# synth-zodiac-scorpio-kbd-old.net
KiCad netlist of a schematic drawn in EAGLE
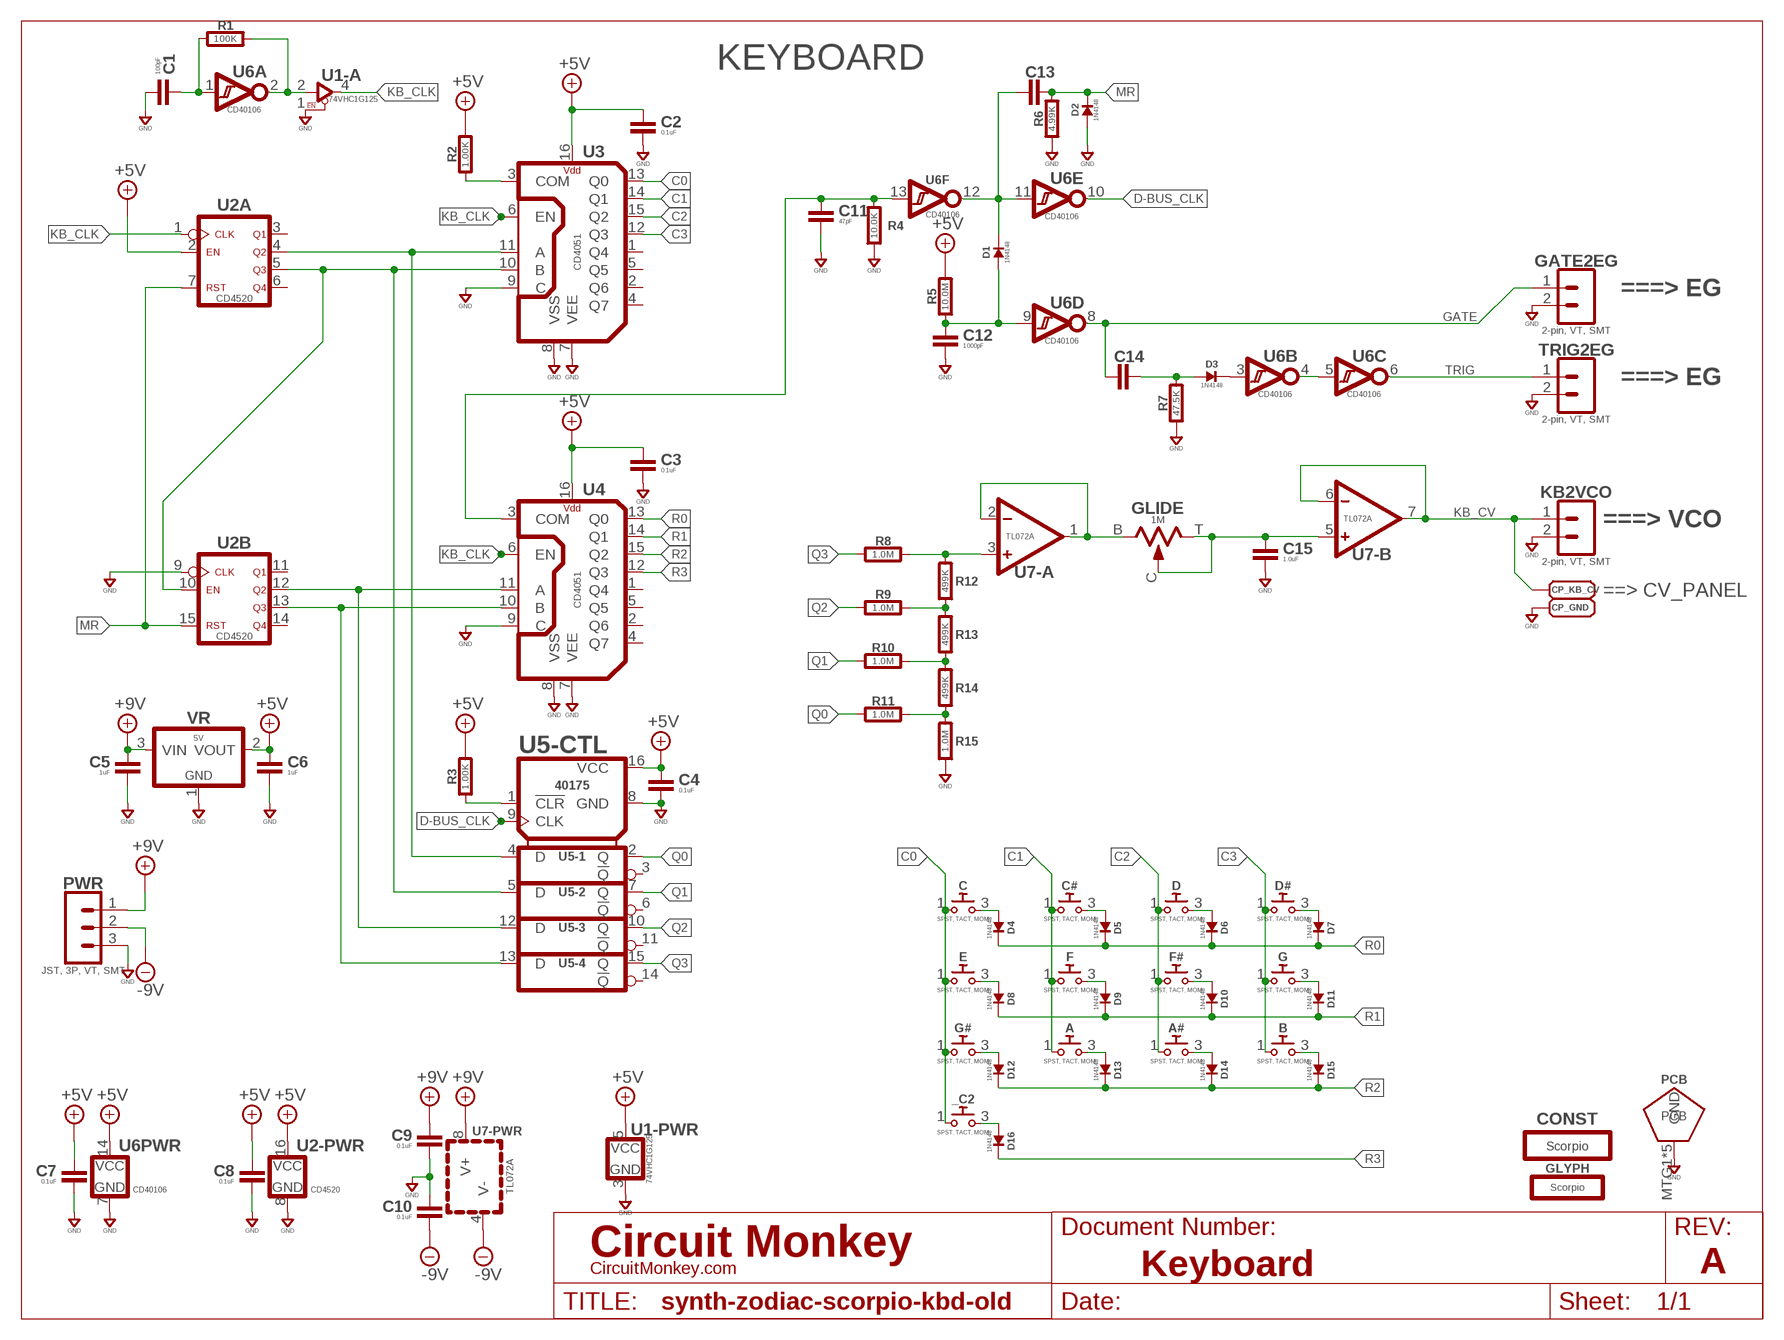
[diagram p0: schematic, sheet 1]

(export (version "E")
  (design (tool "Eeschema 10.0.6"))
  (components
    (comp (ref "A")
      (value "SPST, TACT, MOM")
      (footprint "eagle-import:B3FS-BACKMOUNT")
      (fields (field (name "MFR") "CK") (field (name "MPN") "B3FS"))
      (libsource (lib "eagle-import") (part "PUSHBTN-MOMB3FS-BLIND"))
    )
    (comp (ref "A#")
      (value "SPST, TACT, MOM")
      (footprint "eagle-import:B3FS-BACKMOUNT")
      (fields (field (name "MFR") "CK") (field (name "MPN") "B3FS"))
      (libsource (lib "eagle-import") (part "PUSHBTN-MOMB3FS-BLIND"))
    )
    (comp (ref "B")
      (value "SPST, TACT, MOM")
      (footprint "eagle-import:B3FS-BACKMOUNT")
      (fields (field (name "MFR") "CK") (field (name "MPN") "B3FS"))
      (libsource (lib "eagle-import") (part "PUSHBTN-MOMB3FS-BLIND"))
    )
    (comp (ref "C")
      (value "SPST, TACT, MOM")
      (footprint "eagle-import:B3FS-BACKMOUNT")
      (fields (field (name "MFR") "CK") (field (name "MPN") "B3FS"))
      (libsource (lib "eagle-import") (part "PUSHBTN-MOMB3FS-BLIND"))
    )
    (comp (ref "C#")
      (value "SPST, TACT, MOM")
      (footprint "eagle-import:B3FS-BACKMOUNT")
      (fields (field (name "MFR") "CK") (field (name "MPN") "B3FS"))
      (libsource (lib "eagle-import") (part "PUSHBTN-MOMB3FS-BLIND"))
    )
    (comp (ref "C1")
      (value "100pF")
      (footprint "eagle-import:0603-CAP")
      (libsource (lib "eagle-import") (part "CAPACITOR0603"))
    )
    (comp (ref "C2")
      (value "0.1uF")
      (footprint "eagle-import:0603-CAP")
      (libsource (lib "eagle-import") (part "CAPACITOR0603"))
    )
    (comp (ref "C3")
      (value "0.1uF")
      (footprint "eagle-import:0603-CAP")
      (libsource (lib "eagle-import") (part "CAPACITOR0603"))
    )
    (comp (ref "C4")
      (value "0.1uF")
      (footprint "eagle-import:0603-CAP")
      (libsource (lib "eagle-import") (part "CAPACITOR0603"))
    )
    (comp (ref "C5")
      (value "1uF")
      (footprint "eagle-import:0603-CAP")
      (libsource (lib "eagle-import") (part "CAPACITOR0603"))
    )
    (comp (ref "C6")
      (value "1uF")
      (footprint "eagle-import:0603-CAP")
      (libsource (lib "eagle-import") (part "CAPACITOR0603"))
    )
    (comp (ref "C7")
      (value "0.1uF")
      (footprint "eagle-import:0603-CAP")
      (libsource (lib "eagle-import") (part "CAPACITOR0603"))
    )
    (comp (ref "C8")
      (value "0.1uF")
      (footprint "eagle-import:0603-CAP")
      (libsource (lib "eagle-import") (part "CAPACITOR0603"))
    )
    (comp (ref "C9")
      (value "0.1uF")
      (footprint "eagle-import:0603-CAP")
      (libsource (lib "eagle-import") (part "CAPACITOR0603"))
    )
    (comp (ref "C10")
      (value "0.1uF")
      (footprint "eagle-import:0603-CAP")
      (libsource (lib "eagle-import") (part "CAPACITOR0603"))
    )
    (comp (ref "C11")
      (value "47pF")
      (footprint "eagle-import:0603-CAP")
      (libsource (lib "eagle-import") (part "CAPACITOR0603"))
    )
    (comp (ref "C12")
      (value "1000pF")
      (footprint "eagle-import:0603-CAP")
      (libsource (lib "eagle-import") (part "CAPACITOR0603"))
    )
    (comp (ref "C13")
      (value "220pF")
      (footprint "eagle-import:0603-CAP")
      (libsource (lib "eagle-import") (part "CAPACITOR0603"))
    )
    (comp (ref "C14")
      (value "0.1uF")
      (footprint "eagle-import:0603-CAP")
      (libsource (lib "eagle-import") (part "CAPACITOR0603"))
    )
    (comp (ref "C15")
      (value "1.0uF")
      (footprint "eagle-import:0603-CAP")
      (libsource (lib "eagle-import") (part "CAPACITOR0603"))
    )
    (comp (ref "CONST")
      (value "Scorpio")
      (footprint "eagle-import:SCORPIO-CONST")
      (libsource (lib "eagle-import") (part "CONSTELLATION-SCORPIO"))
    )
    (comp (ref "CP_GND")
      (value "PAD-70X70SMD-070X070")
      (footprint "eagle-import:SMD-070MIL")
      (libsource (lib "eagle-import") (part "PAD-70X70SMD-070X070"))
    )
    (comp (ref "CP_KB_CV")
      (value "PAD-70X70SMD-070X070")
      (footprint "eagle-import:SMD-070MIL")
      (libsource (lib "eagle-import") (part "PAD-70X70SMD-070X070"))
    )
    (comp (ref "D")
      (value "SPST, TACT, MOM")
      (footprint "eagle-import:B3FS-BACKMOUNT")
      (fields (field (name "MFR") "CK") (field (name "MPN") "B3FS"))
      (libsource (lib "eagle-import") (part "PUSHBTN-MOMB3FS-BLIND"))
    )
    (comp (ref "D#")
      (value "SPST, TACT, MOM")
      (footprint "eagle-import:B3FS-BACKMOUNT")
      (fields (field (name "MFR") "CK") (field (name "MPN") "B3FS"))
      (libsource (lib "eagle-import") (part "PUSHBTN-MOMB3FS-BLIND"))
    )
    (comp (ref "D1")
      (value "1N4148")
      (footprint "eagle-import:SOD-123")
      (fields (field (name "MPN") "1N4148W"))
      (libsource (lib "eagle-import") (part "DIODE-1N4148"))
    )
    (comp (ref "D2")
      (value "1N4148")
      (footprint "eagle-import:SOD-123")
      (fields (field (name "MPN") "1N4148W"))
      (libsource (lib "eagle-import") (part "DIODE-1N4148"))
    )
    (comp (ref "D3")
      (value "1N4148")
      (footprint "eagle-import:SOD-123")
      (fields (field (name "MPN") "1N4148W"))
      (libsource (lib "eagle-import") (part "DIODE-1N4148"))
    )
    (comp (ref "D4")
      (value "1N4148")
      (footprint "eagle-import:SOD-123")
      (fields (field (name "MPN") "1N4148W"))
      (libsource (lib "eagle-import") (part "DIODE-1N4148"))
    )
    (comp (ref "D5")
      (value "1N4148")
      (footprint "eagle-import:SOD-123")
      (fields (field (name "MPN") "1N4148W"))
      (libsource (lib "eagle-import") (part "DIODE-1N4148"))
    )
    (comp (ref "D6")
      (value "1N4148")
      (footprint "eagle-import:SOD-123")
      (fields (field (name "MPN") "1N4148W"))
      (libsource (lib "eagle-import") (part "DIODE-1N4148"))
    )
    (comp (ref "D7")
      (value "1N4148")
      (footprint "eagle-import:SOD-123")
      (fields (field (name "MPN") "1N4148W"))
      (libsource (lib "eagle-import") (part "DIODE-1N4148"))
    )
    (comp (ref "D8")
      (value "1N4148")
      (footprint "eagle-import:SOD-123")
      (fields (field (name "MPN") "1N4148W"))
      (libsource (lib "eagle-import") (part "DIODE-1N4148"))
    )
    (comp (ref "D9")
      (value "1N4148")
      (footprint "eagle-import:SOD-123")
      (fields (field (name "MPN") "1N4148W"))
      (libsource (lib "eagle-import") (part "DIODE-1N4148"))
    )
    (comp (ref "D10")
      (value "1N4148")
      (footprint "eagle-import:SOD-123")
      (fields (field (name "MPN") "1N4148W"))
      (libsource (lib "eagle-import") (part "DIODE-1N4148"))
    )
    (comp (ref "D11")
      (value "1N4148")
      (footprint "eagle-import:SOD-123")
      (fields (field (name "MPN") "1N4148W"))
      (libsource (lib "eagle-import") (part "DIODE-1N4148"))
    )
    (comp (ref "D12")
      (value "1N4148")
      (footprint "eagle-import:SOD-123")
      (fields (field (name "MPN") "1N4148W"))
      (libsource (lib "eagle-import") (part "DIODE-1N4148"))
    )
    (comp (ref "D13")
      (value "1N4148")
      (footprint "eagle-import:SOD-123")
      (fields (field (name "MPN") "1N4148W"))
      (libsource (lib "eagle-import") (part "DIODE-1N4148"))
    )
    (comp (ref "D14")
      (value "1N4148")
      (footprint "eagle-import:SOD-123")
      (fields (field (name "MPN") "1N4148W"))
      (libsource (lib "eagle-import") (part "DIODE-1N4148"))
    )
    (comp (ref "D15")
      (value "1N4148")
      (footprint "eagle-import:SOD-123")
      (fields (field (name "MPN") "1N4148W"))
      (libsource (lib "eagle-import") (part "DIODE-1N4148"))
    )
    (comp (ref "D16")
      (value "1N4148")
      (footprint "eagle-import:SOD-123")
      (fields (field (name "MPN") "1N4148W"))
      (libsource (lib "eagle-import") (part "DIODE-1N4148"))
    )
    (comp (ref "E")
      (value "SPST, TACT, MOM")
      (footprint "eagle-import:B3FS-BACKMOUNT")
      (fields (field (name "MFR") "CK") (field (name "MPN") "B3FS"))
      (libsource (lib "eagle-import") (part "PUSHBTN-MOMB3FS-BLIND"))
    )
    (comp (ref "F")
      (value "SPST, TACT, MOM")
      (footprint "eagle-import:B3FS-BACKMOUNT")
      (fields (field (name "MFR") "CK") (field (name "MPN") "B3FS"))
      (libsource (lib "eagle-import") (part "PUSHBTN-MOMB3FS-BLIND"))
    )
    (comp (ref "F#")
      (value "SPST, TACT, MOM")
      (footprint "eagle-import:B3FS-BACKMOUNT")
      (fields (field (name "MFR") "CK") (field (name "MPN") "B3FS"))
      (libsource (lib "eagle-import") (part "PUSHBTN-MOMB3FS-BLIND"))
    )
    (comp (ref "G")
      (value "SPST, TACT, MOM")
      (footprint "eagle-import:B3FS-BACKMOUNT")
      (fields (field (name "MFR") "CK") (field (name "MPN") "B3FS"))
      (libsource (lib "eagle-import") (part "PUSHBTN-MOMB3FS-BLIND"))
    )
    (comp (ref "G#")
      (value "SPST, TACT, MOM")
      (footprint "eagle-import:B3FS-BACKMOUNT")
      (fields (field (name "MFR") "CK") (field (name "MPN") "B3FS"))
      (libsource (lib "eagle-import") (part "PUSHBTN-MOMB3FS-BLIND"))
    )
    (comp (ref "GATE2EG")
      (value "2-pin, VT, SMT")
      (footprint "eagle-import:B2B-PH-SM4")
      (fields (field (name "MFR") "JST") (field (name "MPN") "B2B-PH-SM4"))
      (libsource (lib "eagle-import") (part "02PVT-SMT"))
    )
    (comp (ref "GLIDE")
      (value "1M")
      (footprint "eagle-import:POT-RV9110")
      (fields (field (name "MFR") "Tayda") (field (name "MPN") "RV9110NO-OS15A00"))
      (libsource (lib "eagle-import") (part "TRIMPOT9MM_PCB_SHAFT"))
    )
    (comp (ref "GLYPH")
      (value "Scorpio")
      (footprint "eagle-import:SCORPIO-GLYPH")
      (libsource (lib "eagle-import") (part "GLYPH-SCORPIO"))
    )
    (comp (ref "KB2VCO")
      (value "2-pin, VT, SMT")
      (footprint "eagle-import:B2B-PH-SM4")
      (fields (field (name "MFR") "JST") (field (name "MPN") "B2B-PH-SM4"))
      (libsource (lib "eagle-import") (part "02PVT-SMT"))
    )
    (comp (ref "PCB")
      (value "PCB FAB")
      (footprint "eagle-import:PENTAGON-40MM-RAD")
      (libsource (lib "eagle-import") (part "PENTAGON-40R"))
    )
    (comp (ref "PWR")
      (value "JST, 3P, VT, SMT")
      (footprint "eagle-import:B3B-PH-SM4")
      (fields (field (name "MFR") "JST") (field (name "MPN") "B3B-PH-SM4"))
      (libsource (lib "eagle-import") (part "03P-VT-SMT"))
    )
    (comp (ref "R1")
      (value "100K")
      (footprint "eagle-import:0603-RES")
      (libsource (lib "eagle-import") (part "RESISTOR0603"))
    )
    (comp (ref "R2")
      (value "1.00K")
      (footprint "eagle-import:0603-RES")
      (libsource (lib "eagle-import") (part "RESISTOR0603"))
    )
    (comp (ref "R3")
      (value "1.00K")
      (footprint "eagle-import:0603-RES")
      (libsource (lib "eagle-import") (part "RESISTOR0603"))
    )
    (comp (ref "R4")
      (value "10.0K")
      (footprint "eagle-import:0603-RES")
      (libsource (lib "eagle-import") (part "RESISTOR0603"))
    )
    (comp (ref "R5")
      (value "10.0M")
      (footprint "eagle-import:0603-RES")
      (libsource (lib "eagle-import") (part "RESISTOR0603"))
    )
    (comp (ref "R6")
      (value "4.99K")
      (footprint "eagle-import:0603-RES")
      (libsource (lib "eagle-import") (part "RESISTOR0603"))
    )
    (comp (ref "R7")
      (value "47.5K")
      (footprint "eagle-import:0603-RES")
      (libsource (lib "eagle-import") (part "RESISTOR0603"))
    )
    (comp (ref "R8")
      (value "1.0M")
      (footprint "eagle-import:0603-RES")
      (libsource (lib "eagle-import") (part "RESISTOR0603"))
    )
    (comp (ref "R9")
      (value "1.0M")
      (footprint "eagle-import:0603-RES")
      (libsource (lib "eagle-import") (part "RESISTOR0603"))
    )
    (comp (ref "R10")
      (value "1.0M")
      (footprint "eagle-import:0603-RES")
      (libsource (lib "eagle-import") (part "RESISTOR0603"))
    )
    (comp (ref "R11")
      (value "1.0M")
      (footprint "eagle-import:0603-RES")
      (libsource (lib "eagle-import") (part "RESISTOR0603"))
    )
    (comp (ref "R12")
      (value "499K")
      (footprint "eagle-import:0603-RES")
      (libsource (lib "eagle-import") (part "RESISTOR0603"))
    )
    (comp (ref "R13")
      (value "499K")
      (footprint "eagle-import:0603-RES")
      (libsource (lib "eagle-import") (part "RESISTOR0603"))
    )
    (comp (ref "R14")
      (value "499K")
      (footprint "eagle-import:0603-RES")
      (libsource (lib "eagle-import") (part "RESISTOR0603"))
    )
    (comp (ref "R15")
      (value "1.0M")
      (footprint "eagle-import:0603-RES")
      (libsource (lib "eagle-import") (part "RESISTOR0603"))
    )
    (comp (ref "TRIG2EG")
      (value "2-pin, VT, SMT")
      (footprint "eagle-import:B2B-PH-SM4")
      (fields (field (name "MFR") "JST") (field (name "MPN") "B2B-PH-SM4"))
      (libsource (lib "eagle-import") (part "02PVT-SMT"))
    )
    (comp (ref "U1")
      (value "74VHC1G125")
      (footprint "eagle-import:TSOP-5")
      (fields (field (name "MFR") "ON Semi") (field (name "MPN") "MC74VHC1G125P5TG"))
      (libsource (lib "eagle-import") (part "74VHC1G125CMOS-SOT553"))
    )
    (comp (ref "U2")
      (value "CD4520")
      (footprint "eagle-import:SO16")
      (fields (field (name "MFR") "TI") (field (name "MPN") "CD4520BM96"))
      (libsource (lib "eagle-import") (part "CD4520"))
    )
    (comp (ref "U3")
      (value "CD4051")
      (footprint "eagle-import:SO16")
      (fields (field (name "MFR") "TI") (field (name "MPN") "CD4051BM"))
      (libsource (lib "eagle-import") (part "CD4051SO-D"))
    )
    (comp (ref "U4")
      (value "CD4051")
      (footprint "eagle-import:SO16")
      (fields (field (name "MFR") "TI") (field (name "MPN") "CD4051BM"))
      (libsource (lib "eagle-import") (part "CD4051SO-D"))
    )
    (comp (ref "U5")
      (value "40175")
      (footprint "eagle-import:SO16")
      (fields (field (name "MFR") "TI") (field (name "MPN") "CD40175BM"))
      (libsource (lib "eagle-import") (part "CD40175SMT-D-TYPE"))
    )
    (comp (ref "U6")
      (value "CD40106")
      (footprint "eagle-import:SOP14")
      (fields (field (name "MFR") "TI") (field (name "MPN") "CD40106BM"))
      (libsource (lib "eagle-import") (part "CD40106-SOP14"))
    )
    (comp (ref "U7")
      (value "TL072A")
      (footprint "eagle-import:SOP08")
      (fields (field (name "MFR") "ST"))
      (libsource (lib "eagle-import") (part "DUALTL072A"))
    )
    (comp (ref "VR")
      (value "5V")
      (footprint "eagle-import:SOT-23")
      (fields (field (name "MFR") "Diodes, Inc.") (field (name "MPN") "AP7387-50SA"))
      (libsource (lib "eagle-import") (part "LDO-3P--5V-SOT23"))
    )
    (comp (ref "_C2")
      (value "SPST, TACT, MOM")
      (footprint "eagle-import:B3FS-BACKMOUNT")
      (fields (field (name "MFR") "CK") (field (name "MPN") "B3FS"))
      (libsource (lib "eagle-import") (part "PUSHBTN-MOMB3FS-BLIND"))
    )
  )
  (nets
    (net (code "1") (name "+5V") (class "Default")
      (node (ref "C2") (pin "1") (pinfunction "1_1") (pintype "passive"))
      (node (ref "C3") (pin "1") (pinfunction "1_1") (pintype "passive"))
      (node (ref "C4") (pin "1") (pinfunction "1_1") (pintype "passive"))
      (node (ref "C6") (pin "1") (pinfunction "1_1") (pintype "passive"))
      (node (ref "C7") (pin "1") (pinfunction "1_1") (pintype "passive"))
      (node (ref "C8") (pin "1") (pinfunction "1_1") (pintype "passive"))
      (node (ref "R2") (pin "2") (pinfunction "2_2") (pintype "passive"))
      (node (ref "R3") (pin "2") (pinfunction "2_2") (pintype "passive"))
      (node (ref "R5") (pin "2") (pinfunction "2_2") (pintype "passive"))
      (node (ref "U1") (pin "5") (pinfunction "VCC_5") (pintype "power_in"))
      (node (ref "U2") (pin "16") (pinfunction "VCC_16") (pintype "power_in"))
      (node (ref "U2") (pin "2") (pinfunction "EN_2") (pintype "input"))
      (node (ref "U3") (pin "16") (pinfunction "VDD_16") (pintype "power_in"))
      (node (ref "U4") (pin "16") (pinfunction "VDD_16") (pintype "power_in"))
      (node (ref "U5") (pin "16") (pinfunction "VCC_16") (pintype "power_in"))
      (node (ref "U6") (pin "14") (pinfunction "VCC_14") (pintype "power_in"))
      (node (ref "VR") (pin "2") (pinfunction "VOUT_2") (pintype "power_in"))
    )
    (net (code "2") (name "+9V") (class "Default")
      (node (ref "C5") (pin "1") (pinfunction "1_1") (pintype "passive"))
      (node (ref "C9") (pin "1") (pinfunction "1_1") (pintype "passive"))
      (node (ref "PWR") (pin "1") (pinfunction "1_1") (pintype "passive"))
      (node (ref "U7") (pin "8") (pinfunction "V+_8") (pintype "power_in"))
      (node (ref "VR") (pin "3") (pinfunction "VIN_3") (pintype "power_in"))
    )
    (net (code "3") (name "-9V") (class "Default")
      (node (ref "C10") (pin "2") (pinfunction "2_2") (pintype "passive"))
      (node (ref "PWR") (pin "2") (pinfunction "2_2") (pintype "passive"))
      (node (ref "U7") (pin "4") (pinfunction "V-_4") (pintype "power_in"))
    )
    (net (code "4") (name "/GATE") (class "Default")
      (node (ref "C14") (pin "1") (pinfunction "1_1") (pintype "passive"))
      (node (ref "GATE2EG") (pin "1") (pinfunction "1_1") (pintype "passive"))
      (node (ref "U6") (pin "8") (pinfunction "Y_8") (pintype "bidirectional"))
    )
    (net (code "5") (name "/KB_CV") (class "Default")
      (node (ref "CP_KB_CV") (pin "1") (pinfunction "PAD_1") (pintype "bidirectional"))
      (node (ref "KB2VCO") (pin "1") (pinfunction "1_1") (pintype "passive"))
      (node (ref "U7") (pin "6") (pinfunction "-_6") (pintype "input"))
      (node (ref "U7") (pin "7") (pinfunction "OUT_7") (pintype "output"))
    )
    (net (code "6") (name "/TRIG") (class "Default")
      (node (ref "TRIG2EG") (pin "1") (pinfunction "1_1") (pintype "passive"))
      (node (ref "U6") (pin "6") (pinfunction "Y_6") (pintype "bidirectional"))
    )
    (net (code "7") (name "C0") (class "Default")
      (node (ref "C") (pin "1") (pinfunction "1_1") (pintype "passive"))
      (node (ref "E") (pin "1") (pinfunction "1_1") (pintype "passive"))
      (node (ref "G#") (pin "1") (pinfunction "1_1") (pintype "passive"))
      (node (ref "U3") (pin "13") (pinfunction "Q0_13") (pintype "bidirectional"))
      (node (ref "_C2") (pin "1") (pinfunction "1_1") (pintype "passive"))
    )
    (net (code "8") (name "C1") (class "Default")
      (node (ref "A") (pin "1") (pinfunction "1_1") (pintype "passive"))
      (node (ref "C#") (pin "1") (pinfunction "1_1") (pintype "passive"))
      (node (ref "F") (pin "1") (pinfunction "1_1") (pintype "passive"))
      (node (ref "U3") (pin "14") (pinfunction "Q1_14") (pintype "bidirectional"))
    )
    (net (code "9") (name "C2") (class "Default")
      (node (ref "A#") (pin "1") (pinfunction "1_1") (pintype "passive"))
      (node (ref "D") (pin "1") (pinfunction "1_1") (pintype "passive"))
      (node (ref "F#") (pin "1") (pinfunction "1_1") (pintype "passive"))
      (node (ref "U3") (pin "15") (pinfunction "Q2_15") (pintype "bidirectional"))
    )
    (net (code "10") (name "C3") (class "Default")
      (node (ref "B") (pin "1") (pinfunction "1_1") (pintype "passive"))
      (node (ref "D#") (pin "1") (pinfunction "1_1") (pintype "passive"))
      (node (ref "G") (pin "1") (pinfunction "1_1") (pintype "passive"))
      (node (ref "U3") (pin "12") (pinfunction "Q3_12") (pintype "bidirectional"))
    )
    (net (code "11") (name "D-BUS_CLK") (class "Default")
      (node (ref "U5") (pin "9") (pinfunction "CLK_9") (pintype "input"))
      (node (ref "U6") (pin "10") (pinfunction "Y_10") (pintype "bidirectional"))
    )
    (net (code "12") (name "GND") (class "Default")
      (node (ref "C1") (pin "2") (pinfunction "2_2") (pintype "passive"))
      (node (ref "C10") (pin "1") (pinfunction "1_1") (pintype "passive"))
      (node (ref "C11") (pin "2") (pinfunction "2_2") (pintype "passive"))
      (node (ref "C12") (pin "2") (pinfunction "2_2") (pintype "passive"))
      (node (ref "C15") (pin "2") (pinfunction "2_2") (pintype "passive"))
      (node (ref "C2") (pin "2") (pinfunction "2_2") (pintype "passive"))
      (node (ref "C3") (pin "2") (pinfunction "2_2") (pintype "passive"))
      (node (ref "C4") (pin "2") (pinfunction "2_2") (pintype "passive"))
      (node (ref "C5") (pin "2") (pinfunction "2_2") (pintype "passive"))
      (node (ref "C6") (pin "2") (pinfunction "2_2") (pintype "passive"))
      (node (ref "C7") (pin "2") (pinfunction "2_2") (pintype "passive"))
      (node (ref "C8") (pin "2") (pinfunction "2_2") (pintype "passive"))
      (node (ref "C9") (pin "2") (pinfunction "2_2") (pintype "passive"))
      (node (ref "CP_GND") (pin "1") (pinfunction "PAD_1") (pintype "bidirectional"))
      (node (ref "D2") (pin "A") (pinfunction "A_A") (pintype "passive"))
      (node (ref "GATE2EG") (pin "2") (pinfunction "2_2") (pintype "passive"))
      (node (ref "KB2VCO") (pin "2") (pinfunction "2_2") (pintype "passive"))
      (node (ref "PCB") (pin "MTG1") (pinfunction "GND_MTG1") (pintype "bidirectional"))
      (node (ref "PCB") (pin "MTG2") (pinfunction "GND_MTG2") (pintype "bidirectional"))
      (node (ref "PCB") (pin "MTG3") (pinfunction "GND_MTG3") (pintype "bidirectional"))
      (node (ref "PCB") (pin "MTG4") (pinfunction "GND_MTG4") (pintype "bidirectional"))
      (node (ref "PCB") (pin "MTG5") (pinfunction "GND_MTG5") (pintype "bidirectional"))
      (node (ref "PWR") (pin "3") (pinfunction "3_3") (pintype "passive"))
      (node (ref "R15") (pin "1") (pinfunction "1_1") (pintype "passive"))
      (node (ref "R4") (pin "1") (pinfunction "1_1") (pintype "passive"))
      (node (ref "R6") (pin "1") (pinfunction "1_1") (pintype "passive"))
      (node (ref "R7") (pin "1") (pinfunction "1_1") (pintype "passive"))
      (node (ref "TRIG2EG") (pin "2") (pinfunction "2_2") (pintype "passive"))
      (node (ref "U1") (pin "1") (pinfunction "~{EN}_1") (pintype "input"))
      (node (ref "U1") (pin "3") (pinfunction "GND_3") (pintype "power_in"))
      (node (ref "U2") (pin "8") (pinfunction "GND_8") (pintype "power_in"))
      (node (ref "U2") (pin "9") (pinfunction "~{CLK}_9") (pintype "input"))
      (node (ref "U3") (pin "7") (pinfunction "VEE_7") (pintype "power_in"))
      (node (ref "U3") (pin "8") (pinfunction "VSS_8") (pintype "power_in"))
      (node (ref "U3") (pin "9") (pinfunction "C_9") (pintype "input"))
      (node (ref "U4") (pin "7") (pinfunction "VEE_7") (pintype "power_in"))
      (node (ref "U4") (pin "8") (pinfunction "VSS_8") (pintype "power_in"))
      (node (ref "U4") (pin "9") (pinfunction "C_9") (pintype "input"))
      (node (ref "U5") (pin "8") (pinfunction "GND_8") (pintype "power_in"))
      (node (ref "U6") (pin "7") (pinfunction "GND_7") (pintype "power_in"))
      (node (ref "VR") (pin "1") (pinfunction "GND_1") (pintype "power_in"))
    )
    (net (code "13") (name "KB_CLK") (class "Default")
      (node (ref "U1") (pin "4") (pinfunction "Y_4") (pintype "output"))
      (node (ref "U2") (pin "1") (pinfunction "~{CLK}_1") (pintype "input"))
      (node (ref "U3") (pin "6") (pinfunction "EN_6") (pintype "input"))
      (node (ref "U4") (pin "6") (pinfunction "EN_6") (pintype "input"))
    )
    (net (code "14") (name "MR") (class "Default")
      (node (ref "C13") (pin "2") (pinfunction "2_2") (pintype "passive"))
      (node (ref "D2") (pin "K") (pinfunction "K_K") (pintype "passive"))
      (node (ref "R6") (pin "2") (pinfunction "2_2") (pintype "passive"))
      (node (ref "U2") (pin "15") (pinfunction "RST_15") (pintype "input"))
      (node (ref "U2") (pin "7") (pinfunction "RST_7") (pintype "input"))
    )
    (net (code "15") (name "Net-(A#-2)") (class "Default")
      (node (ref "A#") (pin "3") (pinfunction "2_3") (pintype "passive"))
      (node (ref "D14") (pin "A") (pinfunction "A_A") (pintype "passive"))
    )
    (net (code "16") (name "Net-(A-2)") (class "Default")
      (node (ref "A") (pin "3") (pinfunction "2_3") (pintype "passive"))
      (node (ref "D13") (pin "A") (pinfunction "A_A") (pintype "passive"))
    )
    (net (code "17") (name "Net-(B-2)") (class "Default")
      (node (ref "B") (pin "3") (pinfunction "2_3") (pintype "passive"))
      (node (ref "D15") (pin "A") (pinfunction "A_A") (pintype "passive"))
    )
    (net (code "18") (name "Net-(C#-2)") (class "Default")
      (node (ref "C#") (pin "3") (pinfunction "2_3") (pintype "passive"))
      (node (ref "D5") (pin "A") (pinfunction "A_A") (pintype "passive"))
    )
    (net (code "19") (name "Net-(C-2)") (class "Default")
      (node (ref "C") (pin "3") (pinfunction "2_3") (pintype "passive"))
      (node (ref "D4") (pin "A") (pinfunction "A_A") (pintype "passive"))
    )
    (net (code "20") (name "Net-(C14-Pad2)") (class "Default")
      (node (ref "C14") (pin "2") (pinfunction "2_2") (pintype "passive"))
      (node (ref "D3") (pin "A") (pinfunction "A_A") (pintype "passive"))
      (node (ref "R7") (pin "2") (pinfunction "2_2") (pintype "passive"))
    )
    (net (code "21") (name "Net-(D#-2)") (class "Default")
      (node (ref "D#") (pin "3") (pinfunction "2_3") (pintype "passive"))
      (node (ref "D7") (pin "A") (pinfunction "A_A") (pintype "passive"))
    )
    (net (code "22") (name "Net-(D-2)") (class "Default")
      (node (ref "D") (pin "3") (pinfunction "2_3") (pintype "passive"))
      (node (ref "D6") (pin "A") (pinfunction "A_A") (pintype "passive"))
    )
    (net (code "23") (name "Net-(E-2)") (class "Default")
      (node (ref "D8") (pin "A") (pinfunction "A_A") (pintype "passive"))
      (node (ref "E") (pin "3") (pinfunction "2_3") (pintype "passive"))
    )
    (net (code "24") (name "Net-(F#-2)") (class "Default")
      (node (ref "D10") (pin "A") (pinfunction "A_A") (pintype "passive"))
      (node (ref "F#") (pin "3") (pinfunction "2_3") (pintype "passive"))
    )
    (net (code "25") (name "Net-(F-2)") (class "Default")
      (node (ref "D9") (pin "A") (pinfunction "A_A") (pintype "passive"))
      (node (ref "F") (pin "3") (pinfunction "2_3") (pintype "passive"))
    )
    (net (code "26") (name "Net-(G#-2)") (class "Default")
      (node (ref "D12") (pin "A") (pinfunction "A_A") (pintype "passive"))
      (node (ref "G#") (pin "3") (pinfunction "2_3") (pintype "passive"))
    )
    (net (code "27") (name "Net-(G-2)") (class "Default")
      (node (ref "D11") (pin "A") (pinfunction "A_A") (pintype "passive"))
      (node (ref "G") (pin "3") (pinfunction "2_3") (pintype "passive"))
    )
    (net (code "28") (name "Net-(GLIDE-1)") (class "Default")
      (node (ref "GLIDE") (pin "B") (pinfunction "1_B") (pintype "passive"))
      (node (ref "U7") (pin "1") (pinfunction "OUT_1") (pintype "output"))
      (node (ref "U7") (pin "2") (pinfunction "-_2") (pintype "input"))
    )
    (net (code "29") (name "Net-(GLIDE-2)") (class "Default")
      (node (ref "C15") (pin "1") (pinfunction "1_1") (pintype "passive"))
      (node (ref "GLIDE") (pin "C") (pinfunction "2_C") (pintype "passive"))
      (node (ref "GLIDE") (pin "T") (pinfunction "3_T") (pintype "passive"))
      (node (ref "U7") (pin "5") (pinfunction "+_5") (pintype "input"))
    )
    (net (code "30") (name "Net-(R10-Pad2)") (class "Default")
      (node (ref "R10") (pin "2") (pinfunction "2_2") (pintype "passive"))
      (node (ref "R13") (pin "1") (pinfunction "1_1") (pintype "passive"))
      (node (ref "R14") (pin "2") (pinfunction "2_2") (pintype "passive"))
    )
    (net (code "31") (name "Net-(R11-Pad2)") (class "Default")
      (node (ref "R11") (pin "2") (pinfunction "2_2") (pintype "passive"))
      (node (ref "R14") (pin "1") (pinfunction "1_1") (pintype "passive"))
      (node (ref "R15") (pin "2") (pinfunction "2_2") (pintype "passive"))
    )
    (net (code "32") (name "Net-(R12-Pad1)") (class "Default")
      (node (ref "R12") (pin "1") (pinfunction "1_1") (pintype "passive"))
      (node (ref "R13") (pin "2") (pinfunction "2_2") (pintype "passive"))
      (node (ref "R9") (pin "2") (pinfunction "2_2") (pintype "passive"))
    )
    (net (code "33") (name "Net-(U1A-A)") (class "Default")
      (node (ref "R1") (pin "2") (pinfunction "2_2") (pintype "passive"))
      (node (ref "U1") (pin "2") (pinfunction "A_2") (pintype "input"))
      (node (ref "U6") (pin "2") (pinfunction "Y_2") (pintype "bidirectional"))
    )
    (net (code "34") (name "Net-(U2B-Q2)") (class "Default")
      (node (ref "U2") (pin "4") (pinfunction "Q2_4") (pintype "output"))
      (node (ref "U3") (pin "11") (pinfunction "A_11") (pintype "input"))
      (node (ref "U5") (pin "4") (pinfunction "D_4") (pintype "input"))
    )
    (net (code "35") (name "Net-(U2B-Q3)") (class "Default")
      (node (ref "U2") (pin "10") (pinfunction "EN_10") (pintype "input"))
      (node (ref "U2") (pin "5") (pinfunction "Q3_5") (pintype "output"))
      (node (ref "U3") (pin "10") (pinfunction "B_10") (pintype "input"))
      (node (ref "U5") (pin "5") (pinfunction "D_5") (pintype "input"))
    )
    (net (code "36") (name "Net-(U2C-Q2)") (class "Default")
      (node (ref "U2") (pin "12") (pinfunction "Q2_12") (pintype "output"))
      (node (ref "U4") (pin "11") (pinfunction "A_11") (pintype "input"))
      (node (ref "U5") (pin "12") (pinfunction "D_12") (pintype "input"))
    )
    (net (code "37") (name "Net-(U2C-Q3)") (class "Default")
      (node (ref "U2") (pin "13") (pinfunction "Q3_13") (pintype "output"))
      (node (ref "U4") (pin "10") (pinfunction "B_10") (pintype "input"))
      (node (ref "U5") (pin "13") (pinfunction "D_13") (pintype "input"))
    )
    (net (code "38") (name "Net-(U3-COM)") (class "Default")
      (node (ref "R2") (pin "1") (pinfunction "1_1") (pintype "passive"))
      (node (ref "U3") (pin "3") (pinfunction "COM_3") (pintype "bidirectional"))
    )
    (net (code "39") (name "Net-(U4-COM)") (class "Default")
      (node (ref "C11") (pin "1") (pinfunction "1_1") (pintype "passive"))
      (node (ref "R4") (pin "2") (pinfunction "2_2") (pintype "passive"))
      (node (ref "U4") (pin "3") (pinfunction "COM_3") (pintype "bidirectional"))
      (node (ref "U6") (pin "13") (pinfunction "A_13") (pintype "bidirectional"))
    )
    (net (code "40") (name "Net-(U5E-~{CLR})") (class "Default")
      (node (ref "R3") (pin "1") (pinfunction "1_1") (pintype "passive"))
      (node (ref "U5") (pin "1") (pinfunction "~{CLR}_1") (pintype "input"))
    )
    (net (code "41") (name "Net-(U6A-A)") (class "Default")
      (node (ref "C1") (pin "1") (pinfunction "1_1") (pintype "passive"))
      (node (ref "R1") (pin "1") (pinfunction "1_1") (pintype "passive"))
      (node (ref "U6") (pin "1") (pinfunction "A_1") (pintype "bidirectional"))
    )
    (net (code "42") (name "Net-(U6B-A)") (class "Default")
      (node (ref "D3") (pin "K") (pinfunction "K_K") (pintype "passive"))
      (node (ref "U6") (pin "3") (pinfunction "A_3") (pintype "bidirectional"))
    )
    (net (code "43") (name "Net-(U6B-Y)") (class "Default")
      (node (ref "U6") (pin "4") (pinfunction "Y_4") (pintype "bidirectional"))
      (node (ref "U6") (pin "5") (pinfunction "A_5") (pintype "bidirectional"))
    )
    (net (code "44") (name "Net-(U6D-A)") (class "Default")
      (node (ref "C12") (pin "1") (pinfunction "1_1") (pintype "passive"))
      (node (ref "D1") (pin "A") (pinfunction "A_A") (pintype "passive"))
      (node (ref "R5") (pin "1") (pinfunction "1_1") (pintype "passive"))
      (node (ref "U6") (pin "9") (pinfunction "A_9") (pintype "bidirectional"))
    )
    (net (code "45") (name "Net-(U6E-A)") (class "Default")
      (node (ref "C13") (pin "1") (pinfunction "1_1") (pintype "passive"))
      (node (ref "D1") (pin "K") (pinfunction "K_K") (pintype "passive"))
      (node (ref "U6") (pin "11") (pinfunction "A_11") (pintype "bidirectional"))
      (node (ref "U6") (pin "12") (pinfunction "Y_12") (pintype "bidirectional"))
    )
    (net (code "46") (name "Net-(U7A-+)") (class "Default")
      (node (ref "R12") (pin "2") (pinfunction "2_2") (pintype "passive"))
      (node (ref "R8") (pin "2") (pinfunction "2_2") (pintype "passive"))
      (node (ref "U7") (pin "3") (pinfunction "+_3") (pintype "input"))
    )
    (net (code "47") (name "Net-(_C2-2)") (class "Default")
      (node (ref "D16") (pin "A") (pinfunction "A_A") (pintype "passive"))
      (node (ref "_C2") (pin "3") (pinfunction "2_3") (pintype "passive"))
    )
    (net (code "48") (name "Q0") (class "Default")
      (node (ref "R11") (pin "1") (pinfunction "1_1") (pintype "passive"))
      (node (ref "U5") (pin "2") (pinfunction "Q_2") (pintype "output"))
    )
    (net (code "49") (name "Q1") (class "Default")
      (node (ref "R10") (pin "1") (pinfunction "1_1") (pintype "passive"))
      (node (ref "U5") (pin "7") (pinfunction "Q_7") (pintype "output"))
    )
    (net (code "50") (name "Q2") (class "Default")
      (node (ref "R9") (pin "1") (pinfunction "1_1") (pintype "passive"))
      (node (ref "U5") (pin "10") (pinfunction "Q_10") (pintype "output"))
    )
    (net (code "51") (name "Q3") (class "Default")
      (node (ref "R8") (pin "1") (pinfunction "1_1") (pintype "passive"))
      (node (ref "U5") (pin "15") (pinfunction "Q_15") (pintype "output"))
    )
    (net (code "52") (name "R0") (class "Default")
      (node (ref "D4") (pin "K") (pinfunction "K_K") (pintype "passive"))
      (node (ref "D5") (pin "K") (pinfunction "K_K") (pintype "passive"))
      (node (ref "D6") (pin "K") (pinfunction "K_K") (pintype "passive"))
      (node (ref "D7") (pin "K") (pinfunction "K_K") (pintype "passive"))
      (node (ref "U4") (pin "13") (pinfunction "Q0_13") (pintype "bidirectional"))
    )
    (net (code "53") (name "R1") (class "Default")
      (node (ref "D10") (pin "K") (pinfunction "K_K") (pintype "passive"))
      (node (ref "D11") (pin "K") (pinfunction "K_K") (pintype "passive"))
      (node (ref "D8") (pin "K") (pinfunction "K_K") (pintype "passive"))
      (node (ref "D9") (pin "K") (pinfunction "K_K") (pintype "passive"))
      (node (ref "U4") (pin "14") (pinfunction "Q1_14") (pintype "bidirectional"))
    )
    (net (code "54") (name "R2") (class "Default")
      (node (ref "D12") (pin "K") (pinfunction "K_K") (pintype "passive"))
      (node (ref "D13") (pin "K") (pinfunction "K_K") (pintype "passive"))
      (node (ref "D14") (pin "K") (pinfunction "K_K") (pintype "passive"))
      (node (ref "D15") (pin "K") (pinfunction "K_K") (pintype "passive"))
      (node (ref "U4") (pin "15") (pinfunction "Q2_15") (pintype "bidirectional"))
    )
    (net (code "55") (name "R3") (class "Default")
      (node (ref "D16") (pin "K") (pinfunction "K_K") (pintype "passive"))
      (node (ref "U4") (pin "12") (pinfunction "Q3_12") (pintype "bidirectional"))
    )
    (net (code "56") (name "unconnected-(U2B-Q1-Pad3)") (class "Default")
      (node (ref "U2") (pin "3") (pinfunction "Q1_3") (pintype "output"))
    )
    (net (code "57") (name "unconnected-(U2B-Q4-Pad6)") (class "Default")
      (node (ref "U2") (pin "6") (pinfunction "Q4_6") (pintype "output"))
    )
    (net (code "58") (name "unconnected-(U2C-Q1-Pad11)") (class "Default")
      (node (ref "U2") (pin "11") (pinfunction "Q1_11") (pintype "output"))
    )
    (net (code "59") (name "unconnected-(U2C-Q4-Pad14)") (class "Default")
      (node (ref "U2") (pin "14") (pinfunction "Q4_14") (pintype "output"))
    )
    (net (code "60") (name "unconnected-(U3-Q4-Pad1)") (class "Default")
      (node (ref "U3") (pin "1") (pinfunction "Q4_1") (pintype "bidirectional"))
    )
    (net (code "61") (name "unconnected-(U3-Q5-Pad5)") (class "Default")
      (node (ref "U3") (pin "5") (pinfunction "Q5_5") (pintype "bidirectional"))
    )
    (net (code "62") (name "unconnected-(U3-Q6-Pad2)") (class "Default")
      (node (ref "U3") (pin "2") (pinfunction "Q6_2") (pintype "bidirectional"))
    )
    (net (code "63") (name "unconnected-(U3-Q7-Pad4)") (class "Default")
      (node (ref "U3") (pin "4") (pinfunction "Q7_4") (pintype "bidirectional"))
    )
    (net (code "64") (name "unconnected-(U4-Q4-Pad1)") (class "Default")
      (node (ref "U4") (pin "1") (pinfunction "Q4_1") (pintype "bidirectional"))
    )
    (net (code "65") (name "unconnected-(U4-Q5-Pad5)") (class "Default")
      (node (ref "U4") (pin "5") (pinfunction "Q5_5") (pintype "bidirectional"))
    )
    (net (code "66") (name "unconnected-(U4-Q6-Pad2)") (class "Default")
      (node (ref "U4") (pin "2") (pinfunction "Q6_2") (pintype "bidirectional"))
    )
    (net (code "67") (name "unconnected-(U4-Q7-Pad4)") (class "Default")
      (node (ref "U4") (pin "4") (pinfunction "Q7_4") (pintype "bidirectional"))
    )
    (net (code "68") (name "unconnected-(U5A-~{Q}-Pad3)") (class "Default")
      (node (ref "U5") (pin "3") (pinfunction "~{Q}_3") (pintype "output"))
    )
    (net (code "69") (name "unconnected-(U5B-~{Q}-Pad6)") (class "Default")
      (node (ref "U5") (pin "6") (pinfunction "~{Q}_6") (pintype "output"))
    )
    (net (code "70") (name "unconnected-(U5C-~{Q}-Pad11)") (class "Default")
      (node (ref "U5") (pin "11") (pinfunction "~{Q}_11") (pintype "output"))
    )
    (net (code "71") (name "unconnected-(U5D-~{Q}-Pad14)") (class "Default")
      (node (ref "U5") (pin "14") (pinfunction "~{Q}_14") (pintype "output"))
    )
  )
)
